# EleksTube_IPS_extend.net
KiCad netlist of a schematic drawn in Altium Designer
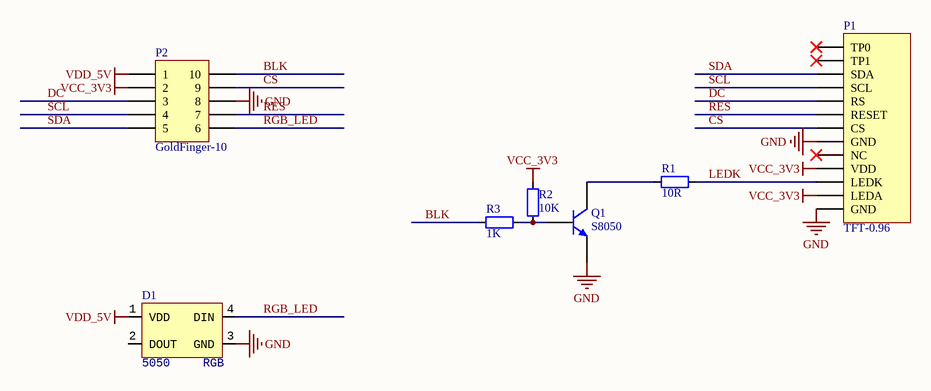
[diagram p0: EleksTube_IPS_extend.SchDoc]

(export (version "E")
  (design (tool "Eeschema 10.0.6"))
  (components
    (comp (ref "D1")
      (value "RGB")
      (footprint "LED_5050_WS2812B")
      (description "LED")
      (fields (field (name "TYPE") "5050"))
      (libsource (lib "KitSprout") (part "LED_5050_WS2812B"))
    )
    (comp (ref "P1")
      (value "TFT-0.96")
      (footprint "TFT-0.96")
      (description "Header, 13-Pin")
      (fields (field (name "PUBLISHER") "Altium Limited"))
      (libsource (lib "20210225_EleksTube_IPS_extend") (part "Header 13"))
    )
    (comp (ref "P2")
      (value "GoldFinger-10")
      (footprint "GoldFinger-10")
      (description "Header, 5-Pin, Dual row")
      (fields (field (name "PUBLISHER") "Altium Limited"))
      (libsource (lib "20210225_EleksTube_IPS_extend") (part "GoldFinger-10"))
    )
    (comp (ref "Q1")
      (value "S8050")
      (footprint "SOT23-3")
      (description "NPN Bipolar Transistor")
      (fields (field (name "PUBLISHER") "Altium Limited"))
      (libsource (lib "Miscellaneous Devices") (part "NPN"))
    )
    (comp (ref "R1")
      (value "10R")
      (footprint "RES_0402")
      (description "Resistor")
      (libsource (lib "MyPcbLib") (part "电阻-0402"))
    )
    (comp (ref "R2")
      (value "10K")
      (footprint "RES_0402")
      (description "Resistor")
      (libsource (lib "") (part "电阻-0402_1"))
    )
    (comp (ref "R3")
      (value "1K")
      (footprint "RES_0402")
      (description "Resistor")
      (libsource (lib "MyPcbLib") (part "电阻-0402"))
    )
  )
  (nets
    (net (code "1") (name "/BLK") (class "Default")
      (node (ref "P2") (pin "10") (pinfunction "10_10") (pintype "passive"))
      (node (ref "R3") (pin "1") (pinfunction "1_1") (pintype "passive"))
    )
    (net (code "2") (name "/CS") (class "Default")
      (node (ref "P1") (pin "7") (pinfunction "CS_7") (pintype "passive"))
      (node (ref "P2") (pin "9") (pinfunction "9_9") (pintype "passive"))
    )
    (net (code "3") (name "/DC") (class "Default")
      (node (ref "P1") (pin "5") (pinfunction "RS_5") (pintype "passive"))
      (node (ref "P2") (pin "3") (pinfunction "3_3") (pintype "passive"))
    )
    (net (code "4") (name "/LEDK") (class "Default")
      (node (ref "P1") (pin "11") (pinfunction "LEDK_11") (pintype "passive"))
      (node (ref "R1") (pin "2") (pinfunction "2_2") (pintype "passive"))
    )
    (net (code "5") (name "/RES") (class "Default")
      (node (ref "P1") (pin "6") (pinfunction "RESET_6") (pintype "passive"))
      (node (ref "P2") (pin "7") (pinfunction "7_7") (pintype "passive"))
    )
    (net (code "6") (name "/RGB_LED") (class "Default")
      (node (ref "D1") (pin "4") (pinfunction "DIN_4") (pintype "passive"))
      (node (ref "P2") (pin "6") (pinfunction "6_6") (pintype "passive"))
    )
    (net (code "7") (name "/SCL") (class "Default")
      (node (ref "P1") (pin "4") (pinfunction "SCL_4") (pintype "passive"))
      (node (ref "P2") (pin "4") (pinfunction "4_4") (pintype "passive"))
    )
    (net (code "8") (name "/SDA") (class "Default")
      (node (ref "P1") (pin "3") (pinfunction "SDA_3") (pintype "passive"))
      (node (ref "P2") (pin "5") (pinfunction "5_5") (pintype "passive"))
    )
    (net (code "9") (name "GND") (class "Default")
      (node (ref "D1") (pin "3") (pinfunction "GND_3") (pintype "passive"))
      (node (ref "P1") (pin "13") (pinfunction "GND_13") (pintype "passive"))
      (node (ref "P1") (pin "8") (pinfunction "GND_8") (pintype "passive"))
      (node (ref "P2") (pin "8") (pinfunction "8_8") (pintype "passive"))
      (node (ref "Q1") (pin "3") (pinfunction "E_3") (pintype "passive"))
    )
    (net (code "10") (name "Net-(Q1-B)") (class "Default")
      (node (ref "Q1") (pin "2") (pinfunction "B_2") (pintype "passive"))
      (node (ref "R2") (pin "1") (pinfunction "1_1") (pintype "passive"))
      (node (ref "R3") (pin "2") (pinfunction "2_2") (pintype "passive"))
    )
    (net (code "11") (name "Net-(Q1-C)") (class "Default")
      (node (ref "Q1") (pin "1") (pinfunction "C_1") (pintype "passive"))
      (node (ref "R1") (pin "1") (pinfunction "1_1") (pintype "passive"))
    )
    (net (code "12") (name "VCC_3V3") (class "Default")
      (node (ref "P1") (pin "10") (pinfunction "VDD_10") (pintype "passive"))
      (node (ref "P1") (pin "12") (pinfunction "LEDA_12") (pintype "passive"))
      (node (ref "P2") (pin "2") (pinfunction "2_2") (pintype "passive"))
      (node (ref "R2") (pin "2") (pinfunction "2_2") (pintype "passive"))
    )
    (net (code "13") (name "VDD_5V") (class "Default")
      (node (ref "D1") (pin "1") (pinfunction "VDD_1") (pintype "passive"))
      (node (ref "P2") (pin "1") (pinfunction "1_1") (pintype "passive"))
    )
    (net (code "14") (name "unconnected-(D1-DOUT-Pad2)") (class "Default")
      (node (ref "D1") (pin "2") (pinfunction "DOUT_2") (pintype "passive"))
    )
    (net (code "15") (name "unconnected-(P1-NC-Pad9)") (class "Default")
      (node (ref "P1") (pin "9") (pinfunction "NC_9") (pintype "passive+no_connect"))
    )
    (net (code "16") (name "unconnected-(P1-TP0-Pad1)") (class "Default")
      (node (ref "P1") (pin "1") (pinfunction "TP0_1") (pintype "passive+no_connect"))
    )
    (net (code "17") (name "unconnected-(P1-TP1-Pad2)") (class "Default")
      (node (ref "P1") (pin "2") (pinfunction "TP1_2") (pintype "passive+no_connect"))
    )
  )
)
